# ReboostV2_Power.net
KiCad netlist of a schematic drawn in Altium Designer
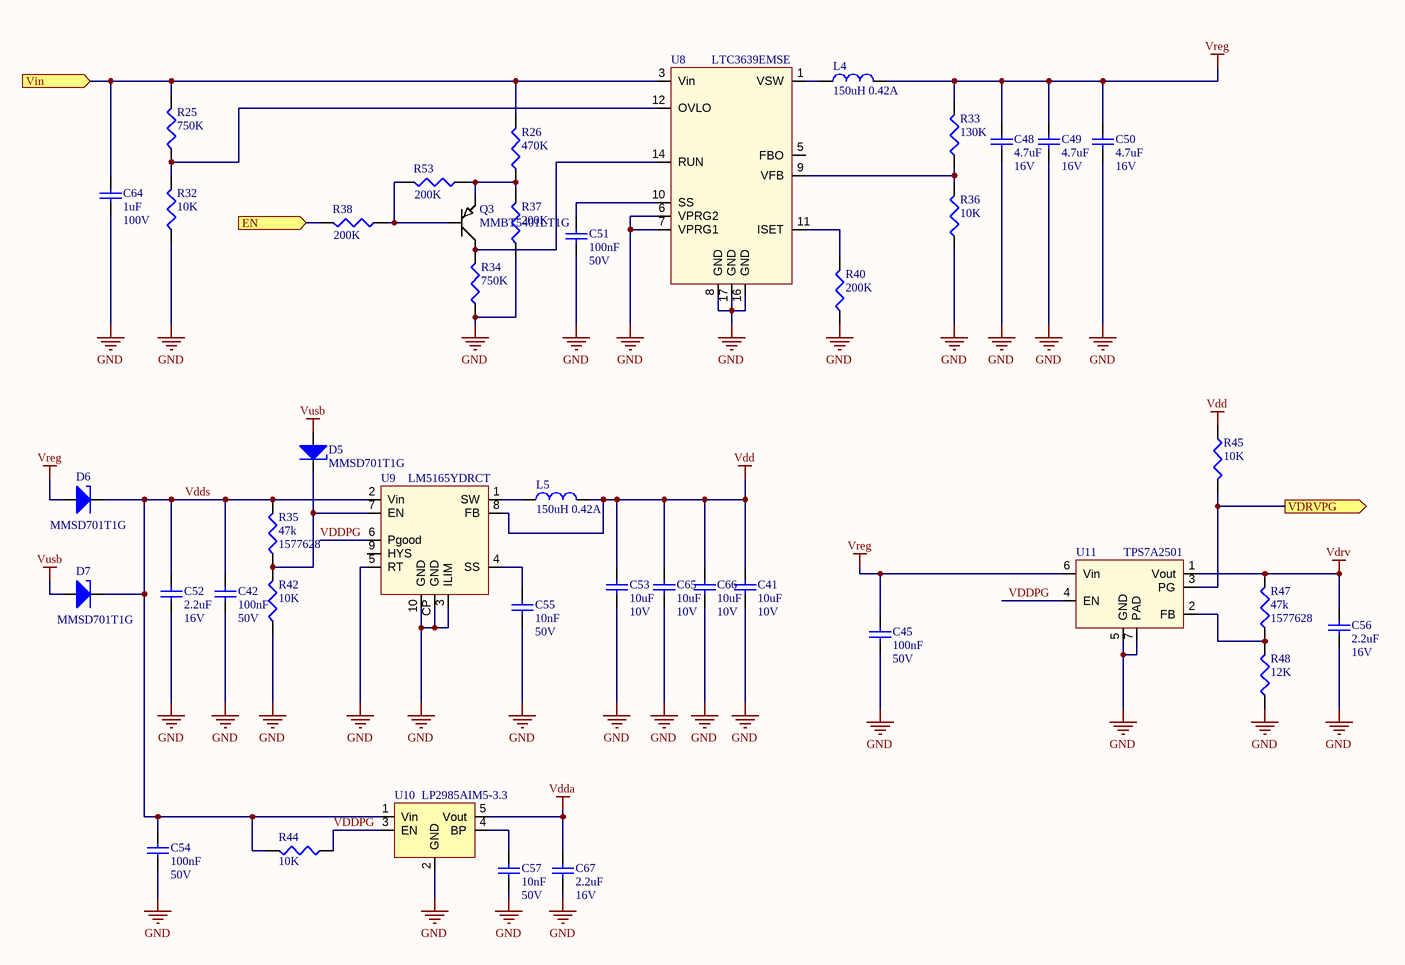
[diagram p0: ReboostV2_Power.SchDoc]

(export (version "E")
  (design (tool "Eeschema 10.0.6"))
  (components
    (comp (ref "C41")
      (value "10uF")
      (footprint "C-0805")
      (description "Capacitor, 10uF, 10V, X7R")
      (fields
        (field (name "VOLTAGE RATING") "10V")
        (field (name "MANUFACTURER") "MURATA")
        (field (name "MANUFACTURER PART NUMBER") "GRM21BR71A106KE51L")
      )
      (libsource (lib "Reboostv2") (part "10uF/0805/CER/10V"))
    )
    (comp (ref "C42")
      (value "100nF")
      (footprint "C0603")
      (description "Capacitor, 100nF, 50V, X7R")
      (fields
        (field (name "VOLTAGE RATING") "50V")
        (field (name "MANUFACTURER") "MULTICOMP")
        (field (name "MANUFACTURER PART NUMBER") "MCCA000255")
      )
      (libsource (lib "Reboostv2") (part "100nF/0603/CER/50V"))
    )
    (comp (ref "C45")
      (value "100nF")
      (footprint "C0603")
      (description "Capacitor, 100nF, 50V, X7R")
      (fields
        (field (name "VOLTAGE RATING") "50V")
        (field (name "MANUFACTURER") "MULTICOMP")
        (field (name "MANUFACTURER PART NUMBER") "MCCA000255")
      )
      (libsource (lib "Reboostv2") (part "100nF/0603/CER/50V"))
    )
    (comp (ref "C48")
      (value "4.7uF")
      (footprint "C-0805")
      (description "Capacitor, 4.7uF, 16V, X7R")
      (fields
        (field (name "VOLTAGE RATING") "16V")
        (field (name "MANUFACTURER") "MURATA")
        (field (name "MANUFACTURER PART NUMBER") "GRM21BR71C475KA73L")
      )
      (libsource (lib "Reboostv2") (part "4.7uF/0805/CER/16V"))
    )
    (comp (ref "C49")
      (value "4.7uF")
      (footprint "C-0805")
      (description "Capacitor, 4.7uF, 16V, X7R")
      (fields
        (field (name "VOLTAGE RATING") "16V")
        (field (name "MANUFACTURER") "MURATA")
        (field (name "MANUFACTURER PART NUMBER") "GRM21BR71C475KA73L")
      )
      (libsource (lib "Reboostv2") (part "4.7uF/0805/CER/16V"))
    )
    (comp (ref "C50")
      (value "4.7uF")
      (footprint "C-0805")
      (description "Capacitor, 4.7uF, 16V, X7R")
      (fields
        (field (name "VOLTAGE RATING") "16V")
        (field (name "MANUFACTURER") "MURATA")
        (field (name "MANUFACTURER PART NUMBER") "GRM21BR71C475KA73L")
      )
      (libsource (lib "Reboostv2") (part "4.7uF/0805/CER/16V"))
    )
    (comp (ref "C51")
      (value "100nF")
      (footprint "C0603")
      (description "Capacitor, 100nF, 50V, X7R")
      (fields
        (field (name "VOLTAGE RATING") "50V")
        (field (name "MANUFACTURER") "MULTICOMP")
        (field (name "MANUFACTURER PART NUMBER") "MCCA000255")
      )
      (libsource (lib "Reboostv2") (part "100nF/0603/CER/50V"))
    )
    (comp (ref "C52")
      (value "2.2uF")
      (footprint "C0603")
      (description "Capacitor, 2.2uF, 16V, X5R")
      (fields
        (field (name "VOLTAGE RATING") "16V")
        (field (name "MANUFACTURER") "MURATA")
        (field (name "MANUFACTURER PART NUMBER") "GRM188R61C225KE15D")
      )
      (libsource (lib "Reboostv2") (part "2.2uF/0603/CER/16V"))
    )
    (comp (ref "C53")
      (value "10uF")
      (footprint "C-0805")
      (description "Capacitor, 10uF, 10V, X7R")
      (fields
        (field (name "VOLTAGE RATING") "10V")
        (field (name "MANUFACTURER") "MURATA")
        (field (name "MANUFACTURER PART NUMBER") "GRM21BR71A106KE51L")
      )
      (libsource (lib "Reboostv2") (part "10uF/0805/CER/10V"))
    )
    (comp (ref "C54")
      (value "100nF")
      (footprint "C0603")
      (description "Capacitor, 100nF, 50V, X7R")
      (fields
        (field (name "VOLTAGE RATING") "50V")
        (field (name "MANUFACTURER") "MULTICOMP")
        (field (name "MANUFACTURER PART NUMBER") "MCCA000255")
      )
      (libsource (lib "Reboostv2") (part "100nF/0603/CER/50V"))
    )
    (comp (ref "C55")
      (value "10nF")
      (footprint "C0603")
      (description "Capacitor, 10nF, 50V, X7R")
      (fields
        (field (name "VOLTAGE RATING") "50V")
        (field (name "MANUFACTURER") "KEMET")
        (field (name "MANUFACTURER PART NUMBER") "C0603C103K5RACTU")
      )
      (libsource (lib "Reboostv2") (part "10nF/0603/CER/50V"))
    )
    (comp (ref "C56")
      (value "2.2uF")
      (footprint "C0603")
      (description "Capacitor, 2.2uF, 16V, X5R")
      (fields
        (field (name "VOLTAGE RATING") "16V")
        (field (name "MANUFACTURER") "MURATA")
        (field (name "MANUFACTURER PART NUMBER") "GRM188R61C225KE15D")
      )
      (libsource (lib "Reboostv2") (part "2.2uF/0603/CER/16V"))
    )
    (comp (ref "C57")
      (value "10nF")
      (footprint "C0603")
      (description "Capacitor, 10nF, 50V, X7R")
      (fields
        (field (name "VOLTAGE RATING") "50V")
        (field (name "MANUFACTURER") "KEMET")
        (field (name "MANUFACTURER PART NUMBER") "C0603C103K5RACTU")
      )
      (libsource (lib "Reboostv2") (part "10nF/0603/CER/50V"))
    )
    (comp (ref "C64")
      (value "1uF")
      (footprint "C-1206")
      (description "Capacitor, 1uF, 100V, X7R")
      (fields
        (field (name "VOLTAGE RATING") "100V")
        (field (name "MANUFACTURER") "AVX")
        (field (name "MANUFACTURER PART NUMBER") "12061C105K4Z2A")
      )
      (libsource (lib "Reboostv2") (part "1uF/1206/CER/100V"))
    )
    (comp (ref "C65")
      (value "10uF")
      (footprint "C-0805")
      (description "Capacitor, 10uF, 10V, X7R")
      (fields
        (field (name "VOLTAGE RATING") "10V")
        (field (name "MANUFACTURER") "MURATA")
        (field (name "MANUFACTURER PART NUMBER") "GRM21BR71A106KE51L")
      )
      (libsource (lib "Reboostv2") (part "10uF/0805/CER/10V"))
    )
    (comp (ref "C66")
      (value "10uF")
      (footprint "C-0805")
      (description "Capacitor, 10uF, 10V, X7R")
      (fields
        (field (name "VOLTAGE RATING") "10V")
        (field (name "MANUFACTURER") "MURATA")
        (field (name "MANUFACTURER PART NUMBER") "GRM21BR71A106KE51L")
      )
      (libsource (lib "Reboostv2") (part "10uF/0805/CER/10V"))
    )
    (comp (ref "C67")
      (value "2.2uF")
      (footprint "C0603")
      (description "Capacitor, 2.2uF, 16V, X5R")
      (fields
        (field (name "VOLTAGE RATING") "16V")
        (field (name "MANUFACTURER") "MURATA")
        (field (name "MANUFACTURER PART NUMBER") "GRM188R61C225KE15D")
      )
      (libsource (lib "Reboostv2") (part "2.2uF/0603/CER/16V"))
    )
    (comp (ref "D5")
      (value "MMSD701T1G")
      (footprint "SOD123 - B")
      (description "Diode Schottky, Vrrm: 70V, If: 0.2A, Vf: 0.5V")
      (fields (field (name "MANUFACTURER") "ON SEMICONDUCTOR"))
      (libsource (lib "Reboostv2") (part "MMSD701T1G"))
    )
    (comp (ref "D6")
      (value "MMSD701T1G")
      (footprint "SOD123 - B")
      (description "Diode Schottky, Vrrm: 70V, If: 0.2A, Vf: 0.5V")
      (fields (field (name "MANUFACTURER") "ON SEMICONDUCTOR"))
      (libsource (lib "Reboostv2") (part "MMSD701T1G"))
    )
    (comp (ref "D7")
      (value "MMSD701T1G")
      (footprint "SOD123 - B")
      (description "Diode Schottky, Vrrm: 70V, If: 0.2A, Vf: 0.5V")
      (fields (field (name "MANUFACTURER") "ON SEMICONDUCTOR"))
      (libsource (lib "Reboostv2") (part "MMSD701T1G"))
    )
    (comp (ref "L4")
      (value "150uH 0.42A")
      (footprint "WE-TPC 4828, MH")
      (description "150UH, 30%, 0.42A")
      (fields
        (field (name "MANUFACTURER") "Wurth Elektronik")
        (field (name "MANUFACTURER PART NUMBER") "744043151")
      )
      (libsource (lib "Reboostv2") (part "744043151"))
    )
    (comp (ref "L5")
      (value "150uH 0.42A")
      (footprint "WE-TPC 4828, MH")
      (description "150UH, 30%, 0.42A")
      (fields
        (field (name "MANUFACTURER") "Wurth Elektronik")
        (field (name "MANUFACTURER PART NUMBER") "744043151")
      )
      (libsource (lib "Reboostv2") (part "744043151"))
    )
    (comp (ref "Q3")
      (value "MMBT5401LT1G")
      (footprint "SOT-23")
      (description "Transistor, PNP, Vce:-150V, Vcb:-160V, Veb:-5V, Ic:-0,5A, Hfe:60 to 240")
      (fields (field (name "MANUFACTURER") "ON SEMICONDUCTOR"))
      (libsource (lib "Reboostv2") (part "MMBT5401LT1G"))
    )
    (comp (ref "R25")
      (value "750K")
      (footprint "0603")
      (description "Resistor, 750K, 1%, 0.063W, 50V, 100PPM, 0603")
      (fields
        (field (name "MANUFACTURER") "VISHAY DRALORIC")
        (field (name "MANUFACTURER PART NUMBER") "CRCW0603750KFKEA")
      )
      (libsource (lib "Reboostv2") (part "750K/0603/0063W/50V"))
    )
    (comp (ref "R26")
      (value "470K")
      (footprint "0603")
      (description "Resistor, 470K, 1%, 0.063W, 50V, 100PPM, 0603")
      (fields
        (field (name "MANUFACTURER") "VISHAY DRALORIC")
        (field (name "MANUFACTURER PART NUMBER") "CRCW0603470KFKEA")
      )
      (libsource (lib "Reboostv2") (part "470K/0603/0063W/50V"))
    )
    (comp (ref "R32")
      (value "10K")
      (footprint "0603")
      (description "Resistor, 10K, 1%, 0.063W, 50V, 100PPM, 0603")
      (fields
        (field (name "MANUFACTURER") "VISHAY DRALORIC")
        (field (name "MANUFACTURER PART NUMBER") "CRCW060310K0FKEA")
      )
      (libsource (lib "Reboostv2") (part "10K/0603/0063W/50V"))
    )
    (comp (ref "R33")
      (value "130K")
      (footprint "0603")
      (description "Resistor, 130K, 1%, 0.063W, 50V, 100PPM, 0603")
      (fields
        (field (name "MANUFACTURER") "VISHAY DRALORIC")
        (field (name "MANUFACTURER PART NUMBER") "CRCW0603130KFKEA")
      )
      (libsource (lib "Reboostv2") (part "130K/0603/0063W/50V"))
    )
    (comp (ref "R34")
      (value "750K")
      (footprint "0603")
      (description "Resistor, 750K, 1%, 0.063W, 50V, 100PPM, 0603")
      (fields
        (field (name "MANUFACTURER") "VISHAY DRALORIC")
        (field (name "MANUFACTURER PART NUMBER") "CRCW0603750KFKEA")
      )
      (libsource (lib "Reboostv2") (part "750K/0603/0063W/50V"))
    )
    (comp (ref "R35")
      (value "47k")
      (footprint "0603")
      (description "Resistor, 47K, 0.1%, 0.063W, 50V, 100PPM, 0603")
      (fields
        (field (name "SUPPLIER PART NUMBER 1") "1577628")
        (field (name "MANUFACTURER") "PANASONIC")
        (field (name "MANUFACTURER PART NUMBER") "ERA3AEB473V")
      )
      (libsource (lib "Reboostv2") (part "47K/0603/0063W/50V_1"))
    )
    (comp (ref "R36")
      (value "10K")
      (footprint "0603")
      (description "Resistor, 10K, 1%, 0.063W, 50V, 100PPM, 0603")
      (fields
        (field (name "MANUFACTURER") "VISHAY DRALORIC")
        (field (name "MANUFACTURER PART NUMBER") "CRCW060310K0FKEA")
      )
      (libsource (lib "Reboostv2") (part "10K/0603/0063W/50V"))
    )
    (comp (ref "R37")
      (value "200K")
      (footprint "0603")
      (description "Resistor, 200K, 1%, 0.063W, 50V, 100PPM, 0603")
      (fields
        (field (name "MANUFACTURER") "VISHAY DRALORIC")
        (field (name "MANUFACTURER PART NUMBER") "CRCW0603200KFKEA")
      )
      (libsource (lib "Reboostv2") (part "200K/0603/0063W/50V"))
    )
    (comp (ref "R38")
      (value "200K")
      (footprint "0603")
      (description "Resistor, 200K, 1%, 0.063W, 50V, 100PPM, 0603")
      (fields
        (field (name "MANUFACTURER") "VISHAY DRALORIC")
        (field (name "MANUFACTURER PART NUMBER") "CRCW0603200KFKEA")
      )
      (libsource (lib "Reboostv2") (part "200K/0603/0063W/50V"))
    )
    (comp (ref "R40")
      (value "200K")
      (footprint "0603")
      (description "Resistor, 200K, 1%, 0.1W, 75V, 100PPM, 0603")
      (fields
        (field (name "MANUFACTURER") "VISHAY DRALORIC")
        (field (name "MANUFACTURER PART NUMBER") "CRCW0603200KFKEA")
      )
      (libsource (lib "Reboostv2") (part "200K/0603/0100W/75V"))
    )
    (comp (ref "R42")
      (value "10K")
      (footprint "0603")
      (description "Resistor, 10K, 1%, 0.063W, 50V, 100PPM, 0603")
      (fields
        (field (name "MANUFACTURER") "VISHAY DRALORIC")
        (field (name "MANUFACTURER PART NUMBER") "CRCW060310K0FKEA")
      )
      (libsource (lib "Reboostv2") (part "10K/0603/0063W/50V"))
    )
    (comp (ref "R44")
      (value "10K")
      (footprint "0603")
      (description "Resistor, 10K, 1%, 0.063W, 50V, 100PPM, 0603")
      (fields
        (field (name "MANUFACTURER") "VISHAY DRALORIC")
        (field (name "MANUFACTURER PART NUMBER") "CRCW060310K0FKEA")
      )
      (libsource (lib "Reboostv2") (part "10K/0603/0063W/50V"))
    )
    (comp (ref "R45")
      (value "10K")
      (footprint "0603")
      (description "Resistor, 10K, 1%, 0.063W, 50V, 100PPM, 0603")
      (fields
        (field (name "MANUFACTURER") "VISHAY DRALORIC")
        (field (name "MANUFACTURER PART NUMBER") "CRCW060310K0FKEA")
      )
      (libsource (lib "Reboostv2") (part "10K/0603/0063W/50V"))
    )
    (comp (ref "R47")
      (value "47k")
      (footprint "0603")
      (description "Resistor, 47K, 0.1%, 0.063W, 50V, 100PPM, 0603")
      (fields
        (field (name "SUPPLIER PART NUMBER 1") "1577628")
        (field (name "MANUFACTURER") "PANASONIC")
        (field (name "MANUFACTURER PART NUMBER") "ERA3AEB473V")
      )
      (libsource (lib "Reboostv2") (part "47K/0603/0063W/50V_1"))
    )
    (comp (ref "R48")
      (value "12K")
      (footprint "0603")
      (description "Resistor, 12K, 1%, 0.063W, 50V, 100PPM, 0603")
      (fields
        (field (name "MANUFACTURER") "VISHAY DRALORIC")
        (field (name "MANUFACTURER PART NUMBER") "CRCW060312K0FKEA")
      )
      (libsource (lib "Reboostv2") (part "12K/0603/0063W/50V"))
    )
    (comp (ref "R53")
      (value "200K")
      (footprint "0603")
      (description "Resistor, 200K, 1%, 0.063W, 50V, 100PPM, 0603")
      (fields
        (field (name "MANUFACTURER") "VISHAY DRALORIC")
        (field (name "MANUFACTURER PART NUMBER") "CRCW0603200KFKEA")
      )
      (libsource (lib "Reboostv2") (part "200K/0603/0063W/50V"))
    )
    (comp (ref "U8")
      (value "LTC3639EMSE")
      (footprint "MSE1612")
      (description "High Efficiency, 150V 100mA Synchronous Step-Down Regulator")
      (fields
        (field (name "MANUFACTURER") "Analog Devices Inc.")
        (field (name "MANUFACTURER PART NUMBER") "LTC3639EMSE#PBF")
      )
      (libsource (lib "Reboostv2") (part "LTC3639EMSE"))
    )
    (comp (ref "U9")
      (value "LM5165YDRCT")
      (footprint "PWSON10")
      (description "Buck Vreg 150mA 3V3 out 5-65Vin")
      (fields (field (name "MANUFACTURER") "Texas Instruments"))
      (libsource (lib "Reboostv2") (part "LM5165Y"))
    )
    (comp (ref "U10")
      (value "LP2985AIM5-3.3")
      (footprint "SOT-23-5")
      (description "LDO, 0.3VDO, 3.3V, 0.15A, 1%")
      (fields
        (field (name "MANUFACTURER") "TEXAS INSTRUMENTS")
        (field (name "MANUFACTURER PART NUMBER") "LP2985AIM5-3.3/NOPB")
      )
      (libsource (lib "Reboostv2") (part "LP2985AIM5-3.3"))
    )
    (comp (ref "U11")
      (value "TPS7A2501")
      (footprint "WSON-6")
      (description "TPS7A25 300-mA,18-V, Ultra-LowIQ, Low-DropoutLinearVoltageRegulatorWith Power-Good")
      (fields (field (name "MANUFACTURER") "Texas Instruments") (field (name "MPN") "TPS7A2501DRVT"))
      (libsource (lib "Reboostv2") (part "TPS7A2501DRVT"))
    )
  )
  (nets
    (net (code "1") (name "/EN") (class "Default")
      (node (ref "R38") (pin "2") (pinfunction "2_2") (pintype "passive"))
    )
    (net (code "2") (name "/VDDPG") (class "Default")
      (node (ref "R44") (pin "1") (pinfunction "1_1") (pintype "passive"))
      (node (ref "U10") (pin "3") (pinfunction "EN_3") (pintype "passive"))
      (node (ref "U11") (pin "4") (pinfunction "EN_4") (pintype "passive"))
      (node (ref "U9") (pin "6") (pinfunction "Pgood_6") (pintype "passive"))
    )
    (net (code "3") (name "/VDRVPG") (class "Default")
      (node (ref "R45") (pin "2") (pinfunction "2_2") (pintype "passive"))
      (node (ref "U11") (pin "3") (pinfunction "PG_3") (pintype "passive"))
    )
    (net (code "4") (name "/Vdds") (class "Default")
      (node (ref "C42") (pin "2") (pinfunction "2_2") (pintype "passive"))
      (node (ref "C52") (pin "2") (pinfunction "2_2") (pintype "passive"))
      (node (ref "C54") (pin "2") (pinfunction "2_2") (pintype "passive"))
      (node (ref "D6") (pin "2") (pinfunction "K_2") (pintype "passive"))
      (node (ref "D7") (pin "2") (pinfunction "K_2") (pintype "passive"))
      (node (ref "R35") (pin "2") (pinfunction "2_2") (pintype "passive"))
      (node (ref "R44") (pin "2") (pinfunction "2_2") (pintype "passive"))
      (node (ref "U10") (pin "1") (pinfunction "Vin_1") (pintype "passive"))
      (node (ref "U9") (pin "2") (pinfunction "Vin_2") (pintype "passive"))
    )
    (net (code "5") (name "/Vin") (class "Default")
      (node (ref "C64") (pin "2") (pinfunction "2_2") (pintype "passive"))
      (node (ref "R25") (pin "2") (pinfunction "2_2") (pintype "passive"))
      (node (ref "R26") (pin "2") (pinfunction "2_2") (pintype "passive"))
      (node (ref "U8") (pin "3") (pinfunction "Vin_3") (pintype "passive"))
    )
    (net (code "6") (name "GND") (class "Default")
      (node (ref "C41") (pin "1") (pinfunction "1_1") (pintype "passive"))
      (node (ref "C42") (pin "1") (pinfunction "1_1") (pintype "passive"))
      (node (ref "C45") (pin "1") (pinfunction "1_1") (pintype "passive"))
      (node (ref "C48") (pin "1") (pinfunction "1_1") (pintype "passive"))
      (node (ref "C49") (pin "1") (pinfunction "1_1") (pintype "passive"))
      (node (ref "C50") (pin "1") (pinfunction "1_1") (pintype "passive"))
      (node (ref "C51") (pin "1") (pinfunction "1_1") (pintype "passive"))
      (node (ref "C52") (pin "1") (pinfunction "1_1") (pintype "passive"))
      (node (ref "C53") (pin "1") (pinfunction "1_1") (pintype "passive"))
      (node (ref "C54") (pin "1") (pinfunction "1_1") (pintype "passive"))
      (node (ref "C55") (pin "1") (pinfunction "1_1") (pintype "passive"))
      (node (ref "C56") (pin "1") (pinfunction "1_1") (pintype "passive"))
      (node (ref "C57") (pin "1") (pinfunction "1_1") (pintype "passive"))
      (node (ref "C64") (pin "1") (pinfunction "1_1") (pintype "passive"))
      (node (ref "C65") (pin "1") (pinfunction "1_1") (pintype "passive"))
      (node (ref "C66") (pin "1") (pinfunction "1_1") (pintype "passive"))
      (node (ref "C67") (pin "1") (pinfunction "1_1") (pintype "passive"))
      (node (ref "R32") (pin "1") (pinfunction "1_1") (pintype "passive"))
      (node (ref "R34") (pin "1") (pinfunction "1_1") (pintype "passive"))
      (node (ref "R36") (pin "1") (pinfunction "1_1") (pintype "passive"))
      (node (ref "R37") (pin "1") (pinfunction "1_1") (pintype "passive"))
      (node (ref "R40") (pin "1") (pinfunction "1_1") (pintype "passive"))
      (node (ref "R42") (pin "1") (pinfunction "1_1") (pintype "passive"))
      (node (ref "R48") (pin "1") (pinfunction "1_1") (pintype "passive"))
      (node (ref "U10") (pin "2") (pinfunction "GND_2") (pintype "passive"))
      (node (ref "U11") (pin "5") (pinfunction "GND_5") (pintype "passive"))
      (node (ref "U11") (pin "7") (pinfunction "PAD_7") (pintype "passive"))
      (node (ref "U8") (pin "16") (pinfunction "GND_16") (pintype "passive"))
      (node (ref "U8") (pin "17") (pinfunction "GND_17") (pintype "passive"))
      (node (ref "U8") (pin "6") (pinfunction "VPRG2_6") (pintype "passive"))
      (node (ref "U8") (pin "7") (pinfunction "VPRG1_7") (pintype "passive"))
      (node (ref "U8") (pin "8") (pinfunction "GND_8") (pintype "passive"))
      (node (ref "U9") (pin "10") (pinfunction "GND_10") (pintype "passive"))
      (node (ref "U9") (pin "3") (pinfunction "ILIM_3") (pintype "passive"))
      (node (ref "U9") (pin "5") (pinfunction "RT_5") (pintype "passive"))
      (node (ref "U9") (pin "CP") (pinfunction "GND_CP") (pintype "passive"))
    )
    (net (code "7") (name "Net-(D5-K)") (class "Default")
      (node (ref "D5") (pin "2") (pinfunction "K_2") (pintype "passive"))
      (node (ref "R35") (pin "1") (pinfunction "1_1") (pintype "passive"))
      (node (ref "R42") (pin "2") (pinfunction "2_2") (pintype "passive"))
      (node (ref "U9") (pin "7") (pinfunction "EN_7") (pintype "passive"))
    )
    (net (code "8") (name "Net-(Q3-Pad1)") (class "Default")
      (node (ref "Q3") (pin "1") (pinfunction "1_1") (pintype "passive"))
      (node (ref "R38") (pin "1") (pinfunction "1_1") (pintype "passive"))
      (node (ref "R53") (pin "2") (pinfunction "2_2") (pintype "passive"))
    )
    (net (code "9") (name "Net-(Q3-Pad2)") (class "Default")
      (node (ref "Q3") (pin "2") (pinfunction "2_2") (pintype "passive"))
      (node (ref "R26") (pin "1") (pinfunction "1_1") (pintype "passive"))
      (node (ref "R37") (pin "2") (pinfunction "2_2") (pintype "passive"))
      (node (ref "R53") (pin "1") (pinfunction "1_1") (pintype "passive"))
    )
    (net (code "10") (name "Net-(U8-ISET)") (class "Default")
      (node (ref "R40") (pin "2") (pinfunction "2_2") (pintype "passive"))
      (node (ref "U8") (pin "11") (pinfunction "ISET_11") (pintype "passive"))
    )
    (net (code "11") (name "Net-(U8-OVLO)") (class "Default")
      (node (ref "R25") (pin "1") (pinfunction "1_1") (pintype "passive"))
      (node (ref "R32") (pin "2") (pinfunction "2_2") (pintype "passive"))
      (node (ref "U8") (pin "12") (pinfunction "OVLO_12") (pintype "passive"))
    )
    (net (code "12") (name "Net-(U8-RUN)") (class "Default")
      (node (ref "Q3") (pin "3") (pinfunction "3_3") (pintype "passive"))
      (node (ref "R34") (pin "2") (pinfunction "2_2") (pintype "passive"))
      (node (ref "U8") (pin "14") (pinfunction "RUN_14") (pintype "passive"))
    )
    (net (code "13") (name "Net-(U8-SS)") (class "Default")
      (node (ref "C51") (pin "2") (pinfunction "2_2") (pintype "passive"))
      (node (ref "U8") (pin "10") (pinfunction "SS_10") (pintype "passive"))
    )
    (net (code "14") (name "Net-(U8-VFB)") (class "Default")
      (node (ref "R33") (pin "1") (pinfunction "1_1") (pintype "passive"))
      (node (ref "R36") (pin "2") (pinfunction "2_2") (pintype "passive"))
      (node (ref "U8") (pin "9") (pinfunction "VFB_9") (pintype "passive"))
    )
    (net (code "15") (name "Net-(U8-VSW)") (class "Default")
      (node (ref "L4") (pin "1") (pinfunction "1_1") (pintype "passive"))
      (node (ref "U8") (pin "1") (pinfunction "VSW_1") (pintype "passive"))
    )
    (net (code "16") (name "Net-(U9-SS)") (class "Default")
      (node (ref "C55") (pin "2") (pinfunction "2_2") (pintype "passive"))
      (node (ref "U9") (pin "4") (pinfunction "SS_4") (pintype "passive"))
    )
    (net (code "17") (name "Net-(U9-SW)") (class "Default")
      (node (ref "L5") (pin "1") (pinfunction "1_1") (pintype "passive"))
      (node (ref "U9") (pin "1") (pinfunction "SW_1") (pintype "passive"))
    )
    (net (code "18") (name "Net-(U10-BP)") (class "Default")
      (node (ref "C57") (pin "2") (pinfunction "2_2") (pintype "passive"))
      (node (ref "U10") (pin "4") (pinfunction "BP_4") (pintype "passive"))
    )
    (net (code "19") (name "Net-(U11-FB)") (class "Default")
      (node (ref "R47") (pin "1") (pinfunction "1_1") (pintype "passive"))
      (node (ref "R48") (pin "2") (pinfunction "2_2") (pintype "passive"))
      (node (ref "U11") (pin "2") (pinfunction "FB_2") (pintype "passive"))
    )
    (net (code "20") (name "Vdd") (class "Default")
      (node (ref "C41") (pin "2") (pinfunction "2_2") (pintype "passive"))
      (node (ref "C53") (pin "2") (pinfunction "2_2") (pintype "passive"))
      (node (ref "C65") (pin "2") (pinfunction "2_2") (pintype "passive"))
      (node (ref "C66") (pin "2") (pinfunction "2_2") (pintype "passive"))
      (node (ref "L5") (pin "2") (pinfunction "2_2") (pintype "passive"))
      (node (ref "R45") (pin "1") (pinfunction "1_1") (pintype "passive"))
      (node (ref "U9") (pin "8") (pinfunction "FB_8") (pintype "passive"))
    )
    (net (code "21") (name "Vdda") (class "Default")
      (node (ref "C67") (pin "2") (pinfunction "2_2") (pintype "passive"))
      (node (ref "U10") (pin "5") (pinfunction "Vout_5") (pintype "passive"))
    )
    (net (code "22") (name "Vdrv") (class "Default")
      (node (ref "C56") (pin "2") (pinfunction "2_2") (pintype "passive"))
      (node (ref "R47") (pin "2") (pinfunction "2_2") (pintype "passive"))
      (node (ref "U11") (pin "1") (pinfunction "Vout_1") (pintype "passive"))
    )
    (net (code "23") (name "Vreg") (class "Default")
      (node (ref "C45") (pin "2") (pinfunction "2_2") (pintype "passive"))
      (node (ref "C48") (pin "2") (pinfunction "2_2") (pintype "passive"))
      (node (ref "C49") (pin "2") (pinfunction "2_2") (pintype "passive"))
      (node (ref "C50") (pin "2") (pinfunction "2_2") (pintype "passive"))
      (node (ref "D6") (pin "1") (pinfunction "A_1") (pintype "passive"))
      (node (ref "L4") (pin "2") (pinfunction "2_2") (pintype "passive"))
      (node (ref "R33") (pin "2") (pinfunction "2_2") (pintype "passive"))
      (node (ref "U11") (pin "6") (pinfunction "Vin_6") (pintype "passive"))
    )
    (net (code "24") (name "Vusb") (class "Default")
      (node (ref "D5") (pin "1") (pinfunction "A_1") (pintype "passive"))
      (node (ref "D7") (pin "1") (pinfunction "A_1") (pintype "passive"))
    )
    (net (code "25") (name "unconnected-(U8-FBO-Pad5)") (class "Default")
      (node (ref "U8") (pin "5") (pinfunction "FBO_5") (pintype "passive"))
    )
    (net (code "26") (name "unconnected-(U9-HYS-Pad9)") (class "Default")
      (node (ref "U9") (pin "9") (pinfunction "HYS_9") (pintype "passive"))
    )
  )
)
